# TB6612.net
KiCad netlist of a schematic drawn in EasyEDA Pro
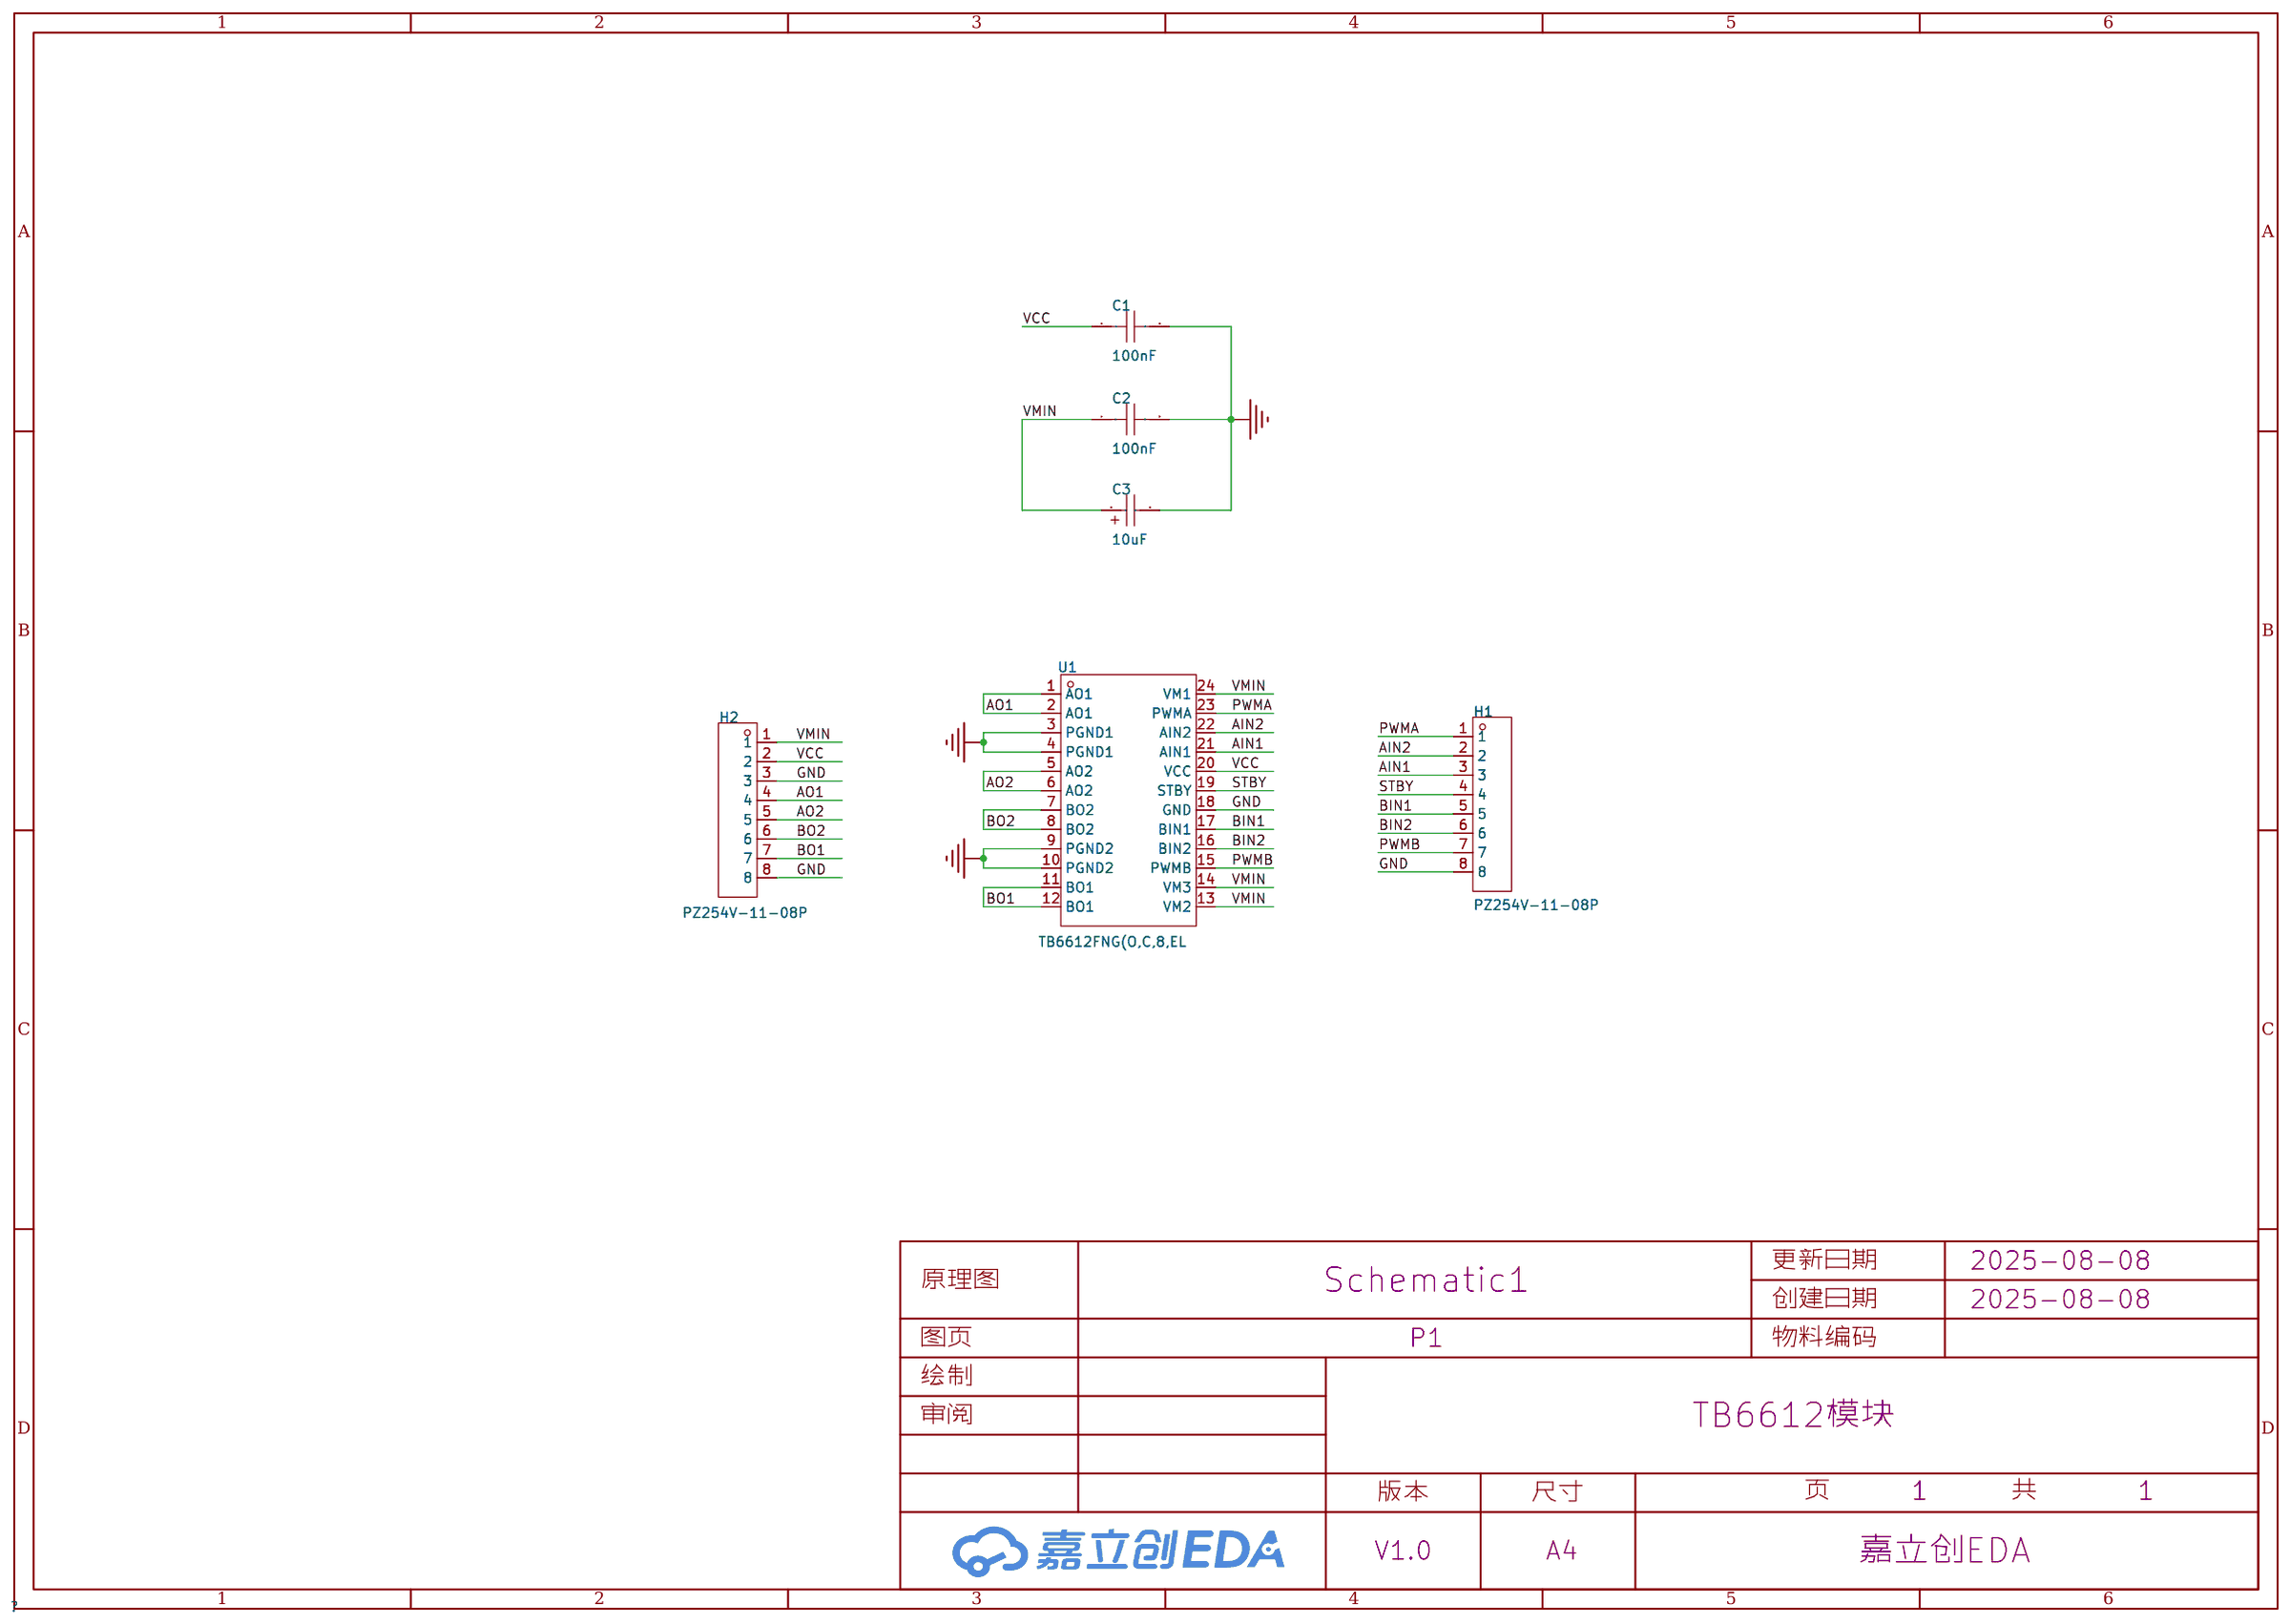
[diagram p0: schematic sheet]

(export (version "E")
  (design (tool "Eeschema 10.0.6"))
  (components
    (comp (ref "C1")
      (value "100nF")
      (footprint "easyedapro:C0603")
      (description "容值:100nF;精度:±10%;额定电压:50V;温度系数:X7R;")
      (fields
        (field (name "Manufacturer Part") "CGA0603X7R104K500JT")
        (field (name "Manufacturer") "HRE(芯声)")
      )
      (libsource (lib "easyedapro") (part "CGA0603X7R104K500JT"))
    )
    (comp (ref "C2")
      (value "100nF")
      (footprint "easyedapro:C0603")
      (description "容值:100nF;精度:±10%;额定电压:50V;温度系数:X7R;")
      (fields
        (field (name "Manufacturer Part") "CGA0603X7R104K500JT")
        (field (name "Manufacturer") "HRE(芯声)")
      )
      (libsource (lib "easyedapro") (part "CGA0603X7R104K500JT"))
    )
    (comp (ref "C3")
      (value "10uF")
      (footprint "easyedapro:CAP-SMD_L3.2-W1.6-RD-C7171")
      (description "容值:10uF;精度:±10%;额定电压:16V;等效串联电阻(ESR):3Ω@100kHz;")
      (fields (field (name "Manufacturer Part") "TAJA106K016RNJ") (field (name "Manufacturer") "Kyocera AVX"))
      (libsource (lib "easyedapro") (part "TAJA106K016RNJ"))
    )
    (comp (ref "H1")
      (value "PZ254V-11-08P")
      (footprint "easyedapro:HDR-TH_8P-P2.54-V-M")
      (fields (field (name "Manufacturer") "XFCN(兴飞)"))
      (libsource (lib "easyedapro") (part "PZ254V-11-08P"))
    )
    (comp (ref "H2")
      (value "PZ254V-11-08P")
      (footprint "easyedapro:HDR-TH_8P-P2.54-V-M")
      (fields (field (name "Manufacturer") "XFCN(兴飞)"))
      (libsource (lib "easyedapro") (part "PZ254V-11-08P"))
    )
    (comp (ref "U1")
      (value "TB6612FNG(O,C,8,EL")
      (footprint "easyedapro:SSOP-24_L8.4-W5.8-P0.65-LS7.8-BL")
      (description "双直流电机驱动器集成电路")
      (fields (field (name "Manufacturer") "TOSHIBA(东芝)"))
      (libsource (lib "easyedapro") (part "TB6612FNG(O,C,8,EL"))
    )
  )
  (nets
    (net (code "1") (name "/AIN1") (class "Default")
      (node (ref "H1") (pin "3") (pinfunction "3_3") (pintype "unspecified"))
      (node (ref "U1") (pin "21") (pinfunction "AIN1_21") (pintype "unspecified"))
    )
    (net (code "2") (name "/AIN2") (class "Default")
      (node (ref "H1") (pin "2") (pinfunction "2_2") (pintype "unspecified"))
      (node (ref "U1") (pin "22") (pinfunction "AIN2_22") (pintype "unspecified"))
    )
    (net (code "3") (name "/AO1") (class "Default")
      (node (ref "H2") (pin "4") (pinfunction "4_4") (pintype "unspecified"))
      (node (ref "U1") (pin "1") (pinfunction "AO1_1") (pintype "unspecified"))
      (node (ref "U1") (pin "2") (pinfunction "AO1_2") (pintype "unspecified"))
    )
    (net (code "4") (name "/AO2") (class "Default")
      (node (ref "H2") (pin "5") (pinfunction "5_5") (pintype "unspecified"))
      (node (ref "U1") (pin "5") (pinfunction "AO2_5") (pintype "unspecified"))
      (node (ref "U1") (pin "6") (pinfunction "AO2_6") (pintype "unspecified"))
    )
    (net (code "5") (name "/BIN1") (class "Default")
      (node (ref "H1") (pin "5") (pinfunction "5_5") (pintype "unspecified"))
      (node (ref "U1") (pin "17") (pinfunction "BIN1_17") (pintype "unspecified"))
    )
    (net (code "6") (name "/BIN2") (class "Default")
      (node (ref "H1") (pin "6") (pinfunction "6_6") (pintype "unspecified"))
      (node (ref "U1") (pin "16") (pinfunction "BIN2_16") (pintype "unspecified"))
    )
    (net (code "7") (name "/BO1") (class "Default")
      (node (ref "H2") (pin "7") (pinfunction "7_7") (pintype "unspecified"))
      (node (ref "U1") (pin "11") (pinfunction "BO1_11") (pintype "unspecified"))
      (node (ref "U1") (pin "12") (pinfunction "BO1_12") (pintype "unspecified"))
    )
    (net (code "8") (name "/BO2") (class "Default")
      (node (ref "H2") (pin "6") (pinfunction "6_6") (pintype "unspecified"))
      (node (ref "U1") (pin "7") (pinfunction "BO2_7") (pintype "unspecified"))
      (node (ref "U1") (pin "8") (pinfunction "BO2_8") (pintype "unspecified"))
    )
    (net (code "9") (name "/PWMA") (class "Default")
      (node (ref "H1") (pin "1") (pinfunction "1_1") (pintype "unspecified"))
      (node (ref "U1") (pin "23") (pinfunction "PWMA_23") (pintype "unspecified"))
    )
    (net (code "10") (name "/PWMB") (class "Default")
      (node (ref "H1") (pin "7") (pinfunction "7_7") (pintype "unspecified"))
      (node (ref "U1") (pin "15") (pinfunction "PWMB_15") (pintype "unspecified"))
    )
    (net (code "11") (name "/STBY") (class "Default")
      (node (ref "H1") (pin "4") (pinfunction "4_4") (pintype "unspecified"))
      (node (ref "U1") (pin "19") (pinfunction "STBY_19") (pintype "unspecified"))
    )
    (net (code "12") (name "/VCC") (class "Default")
      (node (ref "C1") (pin "1") (pinfunction "1_1") (pintype "unspecified"))
      (node (ref "H2") (pin "2") (pinfunction "2_2") (pintype "unspecified"))
      (node (ref "U1") (pin "20") (pinfunction "VCC_20") (pintype "unspecified"))
    )
    (net (code "13") (name "/VMIN") (class "Default")
      (node (ref "C2") (pin "1") (pinfunction "1_1") (pintype "unspecified"))
      (node (ref "C3") (pin "1") (pinfunction "1_1") (pintype "input"))
      (node (ref "H2") (pin "1") (pinfunction "1_1") (pintype "unspecified"))
      (node (ref "U1") (pin "13") (pinfunction "VM2_13") (pintype "unspecified"))
      (node (ref "U1") (pin "14") (pinfunction "VM3_14") (pintype "unspecified"))
      (node (ref "U1") (pin "24") (pinfunction "VM1_24") (pintype "unspecified"))
    )
    (net (code "14") (name "GND") (class "Default")
      (node (ref "C1") (pin "2") (pinfunction "2_2") (pintype "unspecified"))
      (node (ref "C2") (pin "2") (pinfunction "2_2") (pintype "unspecified"))
      (node (ref "C3") (pin "2") (pinfunction "2_2") (pintype "input"))
      (node (ref "H1") (pin "8") (pinfunction "8_8") (pintype "unspecified"))
      (node (ref "H2") (pin "3") (pinfunction "3_3") (pintype "unspecified"))
      (node (ref "H2") (pin "8") (pinfunction "8_8") (pintype "unspecified"))
      (node (ref "U1") (pin "10") (pinfunction "PGND2_10") (pintype "unspecified"))
      (node (ref "U1") (pin "18") (pinfunction "GND_18") (pintype "unspecified"))
      (node (ref "U1") (pin "3") (pinfunction "PGND1_3") (pintype "unspecified"))
      (node (ref "U1") (pin "4") (pinfunction "PGND1_4") (pintype "unspecified"))
      (node (ref "U1") (pin "9") (pinfunction "PGND2_9") (pintype "unspecified"))
    )
  )
)
